# Sheet1.net
KiCad netlist of a schematic drawn in Altium Designer
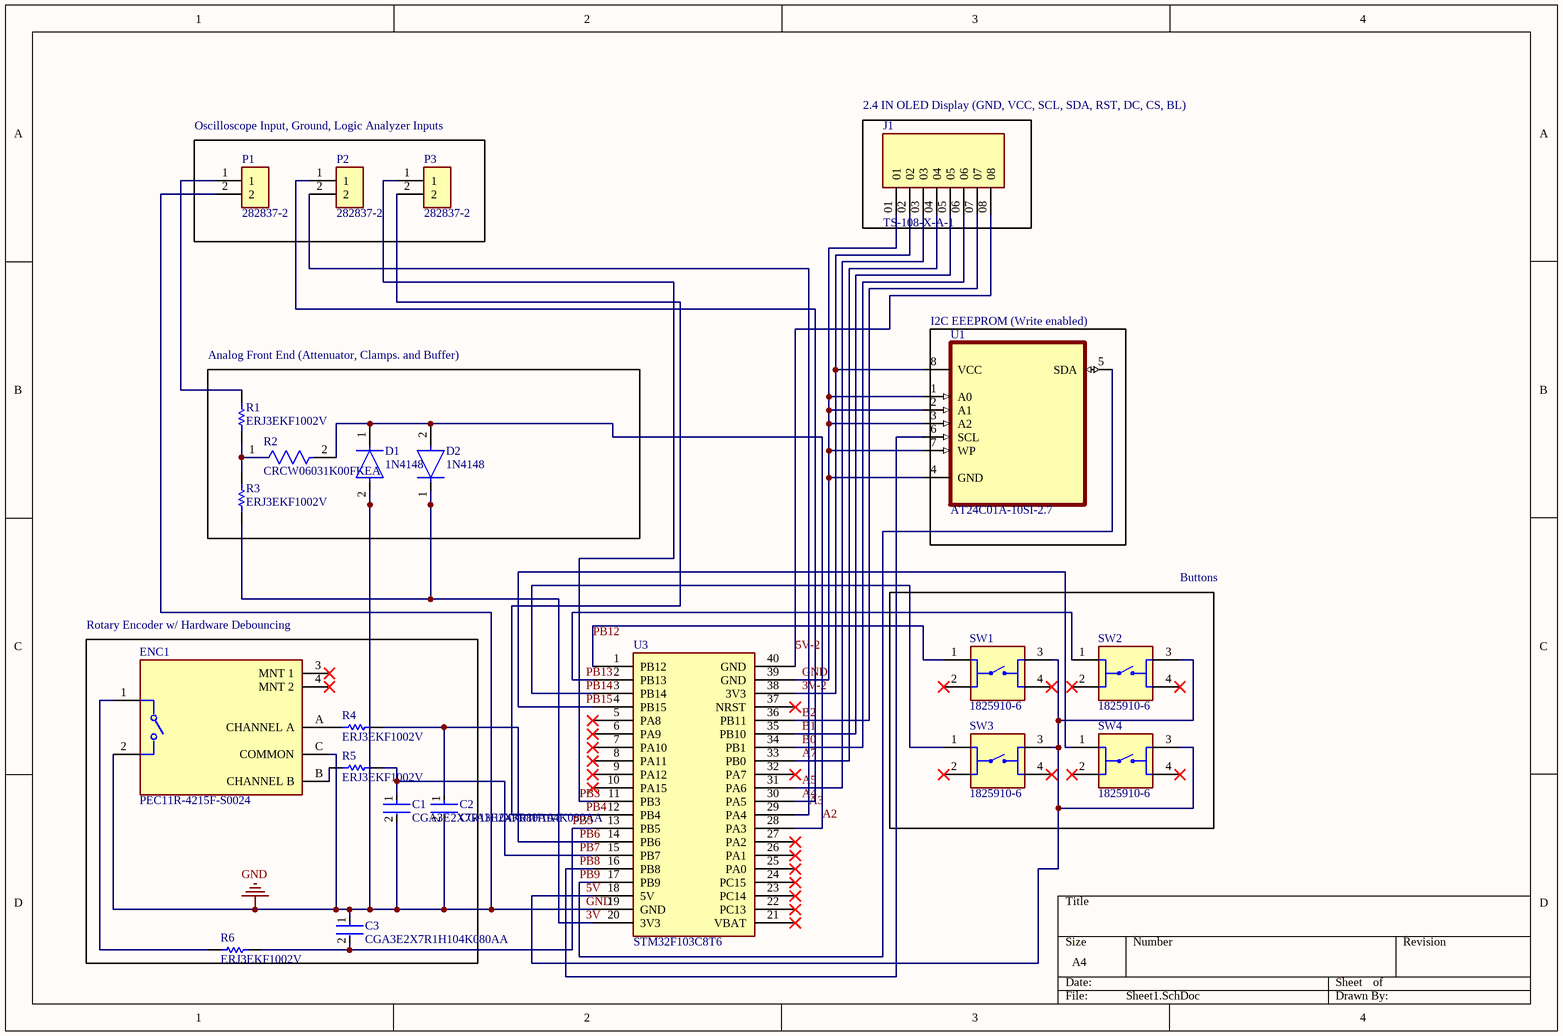
[diagram p0: Sheet1.SchDoc]

(export (version "E")
  (design (tool "Eeschema 10.0.6"))
  (components
    (comp (ref "C1")
      (value "CGA3E2X7R1H104K080AA")
      (footprint "FP-CGA3E-0_3-0_1-IPC_A")
      (description "Cap Ceramic 100nF 50V X7R 10% Pad SMD 0603 +125°C Automotive T/R")
      (fields (field (name "TOLERANCE") "10%") (field (name "VOLTAGE") "50V"))
      (libsource (lib "Altium Content Vault") (part "b4654b650e69147ec39a6b967a45e02"))
    )
    (comp (ref "C2")
      (value "CGA3E2X7R1H104K080AA")
      (footprint "FP-CGA3E-0_3-0_1-IPC_A")
      (description "Cap Ceramic 100nF 50V X7R 10% Pad SMD 0603 +125°C Automotive T/R")
      (fields (field (name "TOLERANCE") "10%") (field (name "VOLTAGE") "50V"))
      (libsource (lib "Altium Content Vault") (part "b4654b650e69147ec39a6b967a45e02"))
    )
    (comp (ref "C3")
      (value "CGA3E2X7R1H104K080AA")
      (footprint "FP-CGA3E-0_3-0_1-IPC_A")
      (description "Cap Ceramic 100nF 50V X7R 10% Pad SMD 0603 +125°C Automotive T/R")
      (fields (field (name "TOLERANCE") "10%") (field (name "VOLTAGE") "50V"))
      (libsource (lib "Altium Content Vault") (part "b4654b650e69147ec39a6b967a45e02"))
    )
    (comp (ref "D1")
      (value "1N4148")
      (footprint "FP-017AG-MFG")
      (description "DIODE GEN PURP 100V 200MA DO35")
      (fields (field (name "VOLTAGE") "100V"))
      (libsource (lib "Altium Content Vault") (part "d7152d700b627762746794eb795d46e"))
    )
    (comp (ref "D2")
      (value "1N4148")
      (footprint "FP-017AG-MFG")
      (description "DIODE GEN PURP 100V 200MA DO35")
      (fields (field (name "VOLTAGE") "100V"))
      (libsource (lib "Altium Content Vault") (part "d7152d700b627762746794eb795d46e"))
    )
    (comp (ref "ENC1")
      (value "PEC11R-4215F-S0024")
      (footprint "FP-PEC11R-4215F-S0024-MFG")
      (description "ROTARY ENCODER MECHANICAL 24PPR")
      (libsource (lib "Altium Content Vault") (part "5f1dd25a4c49fa66e7eeb899730fe11"))
    )
    (comp (ref "J1")
      (value "TS-108-X-A-1")
      (footprint "SAMTEC_TS-108-X-A-1")
      (description "TS Series .100 Single Row Screw Machine Terminal Strip")
      (fields (field (name "MP") "TS-108-G-A-1") (field (name "MF") "Samtec"))
      (libsource (lib "TS-108-X-A-1") (part "TS-108-X-A-1"))
    )
    (comp (ref "P1")
      (value "282837-2")
      (footprint "TE_282837-2")
      (fields (field (name "MF") "TE Connectivity"))
      (libsource (lib "282837-2") (part "282837-2"))
    )
    (comp (ref "P2")
      (value "282837-2")
      (footprint "TE_282837-2")
      (fields (field (name "MF") "TE Connectivity"))
      (libsource (lib "282837-2") (part "282837-2"))
    )
    (comp (ref "P3")
      (value "282837-2")
      (footprint "TE_282837-2")
      (fields (field (name "MF") "TE Connectivity"))
      (libsource (lib "282837-2") (part "282837-2"))
    )
    (comp (ref "R1")
      (value "ERJ3EKF1002V")
      (footprint "RESC1609X55X30LL15T15")
      (description "Chip Resistor, 10 KOhm, +/- 1%, 0.1 W, -55 to 155 degC, 0603 (1608 Metric), RoHS, Tape and Reel")
      (fields (field (name "TOLERANCE") "1%") (field (name "MANUFACTURER") "Panasonic"))
      (libsource (lib "Altium Content Vault") (part "RES-2"))
    )
    (comp (ref "R2")
      (value "CRCW06031K00FKEA")
      (footprint "FP-CRCW0603-e3-MFG")
      (description "RES Thick Film, 1kΩ, 1%, 0.1W, 100ppm/°C, 0603")
      (fields (field (name "TOLERANCE") "1%"))
      (libsource (lib "Altium Content Vault") (part "1029c3af85768c4190bb7ad29bc67b5"))
    )
    (comp (ref "R3")
      (value "ERJ3EKF1002V")
      (footprint "RESC1609X55X30LL15T15")
      (description "Chip Resistor, 10 KOhm, +/- 1%, 0.1 W, -55 to 155 degC, 0603 (1608 Metric), RoHS, Tape and Reel")
      (fields (field (name "TOLERANCE") "1%") (field (name "MANUFACTURER") "Panasonic"))
      (libsource (lib "Altium Content Vault") (part "RES-2"))
    )
    (comp (ref "R4")
      (value "ERJ3EKF1002V")
      (footprint "RESC1609X55X30LL15T15")
      (description "Chip Resistor, 10 KOhm, +/- 1%, 0.1 W, -55 to 155 degC, 0603 (1608 Metric), RoHS, Tape and Reel")
      (fields (field (name "TOLERANCE") "1%") (field (name "MANUFACTURER") "Panasonic"))
      (libsource (lib "Altium Content Vault") (part "RES-2"))
    )
    (comp (ref "R5")
      (value "ERJ3EKF1002V")
      (footprint "RESC1609X55X30LL15T15")
      (description "Chip Resistor, 10 KOhm, +/- 1%, 0.1 W, -55 to 155 degC, 0603 (1608 Metric), RoHS, Tape and Reel")
      (fields (field (name "TOLERANCE") "1%") (field (name "MANUFACTURER") "Panasonic"))
      (libsource (lib "Altium Content Vault") (part "RES-2"))
    )
    (comp (ref "R6")
      (value "ERJ3EKF1002V")
      (footprint "RESC1609X55X30LL15T15")
      (description "Chip Resistor, 10 KOhm, +/- 1%, 0.1 W, -55 to 155 degC, 0603 (1608 Metric), RoHS, Tape and Reel")
      (fields (field (name "TOLERANCE") "1%") (field (name "MANUFACTURER") "Panasonic"))
      (libsource (lib "Altium Content Vault") (part "RES-2"))
    )
    (comp (ref "SW1")
      (value "1825910-6")
      (footprint "SW_1825910-6-4")
      (description "Switch Push Button OFF (ON) SPST Round Button 0.05A 24VDC Momentary Contact PC Pins Thru-Hole")
      (fields (field (name "MF") "TE Connectivity") (field (name "DIGI-KEY_PART_NUMBER") "450-1650-ND"))
      (libsource (lib "1825910-6") (part "1825910-6"))
    )
    (comp (ref "SW2")
      (value "1825910-6")
      (footprint "SW_1825910-6-4")
      (description "Switch Push Button OFF (ON) SPST Round Button 0.05A 24VDC Momentary Contact PC Pins Thru-Hole")
      (fields (field (name "MF") "TE Connectivity") (field (name "DIGI-KEY_PART_NUMBER") "450-1650-ND"))
      (libsource (lib "1825910-6") (part "1825910-6"))
    )
    (comp (ref "SW3")
      (value "1825910-6")
      (footprint "SW_1825910-6-4")
      (description "Switch Push Button OFF (ON) SPST Round Button 0.05A 24VDC Momentary Contact PC Pins Thru-Hole")
      (fields (field (name "MF") "TE Connectivity") (field (name "DIGI-KEY_PART_NUMBER") "450-1650-ND"))
      (libsource (lib "1825910-6") (part "1825910-6"))
    )
    (comp (ref "SW4")
      (value "1825910-6")
      (footprint "SW_1825910-6-4")
      (description "Switch Push Button OFF (ON) SPST Round Button 0.05A 24VDC Momentary Contact PC Pins Thru-Hole")
      (fields (field (name "MF") "TE Connectivity") (field (name "DIGI-KEY_PART_NUMBER") "450-1650-ND"))
      (libsource (lib "1825910-6") (part "1825910-6"))
    )
    (comp (ref "U1")
      (value "AT24C01A-10SI-2.7")
      (footprint "SOIC127P600X175-8N")
      (description "Two-wire Serial EEPROM")
      (libsource (lib "AT24C01A-10SI-2.7") (part "AT24C01A-10SI-2.7"))
    )
    (comp (ref "U3")
      (value "STM32F103C8T6")
      (footprint "ZC323000:MODULE_ZC323000")
      (description "Designed By @Alixahedi")
      (libsource (lib "Stm32 Blue Pill") (part "BluePill"))
    )
  )
  (nets
    (net (code "1") (name "/3V") (class "Default")
      (node (ref "D2") (pin "1") (pinfunction "C_1") (pintype "passive"))
      (node (ref "R3") (pin "2") (pinfunction "2_2") (pintype "passive"))
      (node (ref "U3") (pin "20") (pinfunction "3V3_20") (pintype "passive"))
    )
    (net (code "2") (name "/3V-2") (class "Default")
      (node (ref "J1") (pin "02") (pinfunction "02_02") (pintype "passive"))
      (node (ref "U1") (pin "8") (pinfunction "VCC_8") (pintype "power_in"))
      (node (ref "U3") (pin "38") (pinfunction "3V3_38") (pintype "passive"))
    )
    (net (code "3") (name "/5V") (class "Default")
      (node (ref "SW1") (pin "3") (pinfunction "3_3") (pintype "passive"))
      (node (ref "SW2") (pin "3") (pinfunction "3_3") (pintype "passive"))
      (node (ref "SW3") (pin "3") (pinfunction "3_3") (pintype "passive"))
      (node (ref "SW4") (pin "3") (pinfunction "3_3") (pintype "passive"))
      (node (ref "U3") (pin "18") (pinfunction "5V_18") (pintype "passive"))
    )
    (net (code "4") (name "/5V-2") (class "Default")
      (node (ref "J1") (pin "08") (pinfunction "08_08") (pintype "passive"))
      (node (ref "U3") (pin "40") (pinfunction "GND_40") (pintype "passive"))
    )
    (net (code "5") (name "/A2") (class "Default")
      (node (ref "D1") (pin "1") (pinfunction "C_1") (pintype "passive"))
      (node (ref "D2") (pin "2") (pinfunction "A_2") (pintype "passive"))
      (node (ref "R2") (pin "2") (pinfunction "2_2") (pintype "passive"))
      (node (ref "U3") (pin "28") (pinfunction "PA3_28") (pintype "passive"))
    )
    (net (code "6") (name "/A3") (class "Default")
      (node (ref "P2") (pin "2") (pinfunction "2_2") (pintype "passive"))
      (node (ref "U3") (pin "29") (pinfunction "PA4_29") (pintype "passive"))
    )
    (net (code "7") (name "/A4") (class "Default")
      (node (ref "P2") (pin "1") (pinfunction "1_1") (pintype "passive"))
      (node (ref "U3") (pin "30") (pinfunction "PA5_30") (pintype "passive"))
    )
    (net (code "8") (name "/A5") (class "Default")
      (node (ref "J1") (pin "03") (pinfunction "03_03") (pintype "passive"))
      (node (ref "U3") (pin "31") (pinfunction "PA6_31") (pintype "passive"))
    )
    (net (code "9") (name "/A7") (class "Default")
      (node (ref "J1") (pin "04") (pinfunction "04_04") (pintype "passive"))
      (node (ref "U3") (pin "33") (pinfunction "PB0_33") (pintype "passive"))
    )
    (net (code "10") (name "/B0") (class "Default")
      (node (ref "J1") (pin "06") (pinfunction "06_06") (pintype "passive"))
      (node (ref "U3") (pin "34") (pinfunction "PB1_34") (pintype "passive"))
    )
    (net (code "11") (name "/B1") (class "Default")
      (node (ref "J1") (pin "05") (pinfunction "05_05") (pintype "passive"))
      (node (ref "U3") (pin "35") (pinfunction "PB10_35") (pintype "passive"))
    )
    (net (code "12") (name "/B2") (class "Default")
      (node (ref "J1") (pin "07") (pinfunction "07_07") (pintype "passive"))
      (node (ref "U3") (pin "36") (pinfunction "PB11_36") (pintype "passive"))
    )
    (net (code "13") (name "/PB3") (class "Default")
      (node (ref "P3") (pin "1") (pinfunction "1_1") (pintype "passive"))
      (node (ref "U3") (pin "11") (pinfunction "PB3_11") (pintype "passive"))
    )
    (net (code "14") (name "/PB4") (class "Default")
      (node (ref "P3") (pin "2") (pinfunction "2_2") (pintype "passive"))
      (node (ref "U3") (pin "12") (pinfunction "PB4_12") (pintype "passive"))
    )
    (net (code "15") (name "/PB5") (class "Default")
      (node (ref "C3") (pin "2") (pinfunction "2_2") (pintype "passive"))
      (node (ref "R6") (pin "2") (pinfunction "2_2") (pintype "passive"))
      (node (ref "U3") (pin "13") (pinfunction "PB5_13") (pintype "passive"))
    )
    (net (code "16") (name "/PB6") (class "Default")
      (node (ref "C2") (pin "1") (pinfunction "1_1") (pintype "passive"))
      (node (ref "R4") (pin "2") (pinfunction "2_2") (pintype "passive"))
      (node (ref "U3") (pin "14") (pinfunction "PB6_14") (pintype "passive"))
    )
    (net (code "17") (name "/PB7") (class "Default")
      (node (ref "C1") (pin "1") (pinfunction "1_1") (pintype "passive"))
      (node (ref "R5") (pin "2") (pinfunction "2_2") (pintype "passive"))
      (node (ref "U3") (pin "15") (pinfunction "PB7_15") (pintype "passive"))
    )
    (net (code "18") (name "/PB8") (class "Default")
      (node (ref "U1") (pin "6") (pinfunction "SCL_6") (pintype "input"))
      (node (ref "U3") (pin "16") (pinfunction "PB8_16") (pintype "passive"))
    )
    (net (code "19") (name "/PB9") (class "Default")
      (node (ref "U1") (pin "5") (pinfunction "SDA_5") (pintype "bidirectional"))
      (node (ref "U3") (pin "17") (pinfunction "PB9_17") (pintype "passive"))
    )
    (net (code "20") (name "/PB12") (class "Default")
      (node (ref "SW1") (pin "1") (pinfunction "1_1") (pintype "passive"))
      (node (ref "U3") (pin "1") (pinfunction "PB12_1") (pintype "passive"))
    )
    (net (code "21") (name "/PB13") (class "Default")
      (node (ref "SW2") (pin "1") (pinfunction "1_1") (pintype "passive"))
      (node (ref "U3") (pin "2") (pinfunction "PB13_2") (pintype "passive"))
    )
    (net (code "22") (name "/PB14") (class "Default")
      (node (ref "SW3") (pin "1") (pinfunction "1_1") (pintype "passive"))
      (node (ref "U3") (pin "3") (pinfunction "PB14_3") (pintype "passive"))
    )
    (net (code "23") (name "/PB15") (class "Default")
      (node (ref "SW4") (pin "1") (pinfunction "1_1") (pintype "passive"))
      (node (ref "U3") (pin "4") (pinfunction "PB15_4") (pintype "passive"))
    )
    (net (code "24") (name "GND") (class "Default")
      (node (ref "C1") (pin "2") (pinfunction "2_2") (pintype "passive"))
      (node (ref "C2") (pin "2") (pinfunction "2_2") (pintype "passive"))
      (node (ref "C3") (pin "1") (pinfunction "1_1") (pintype "passive"))
      (node (ref "D1") (pin "2") (pinfunction "A_2") (pintype "passive"))
      (node (ref "ENC1") (pin "2") (pinfunction "2_2") (pintype "passive"))
      (node (ref "ENC1") (pin "C") (pinfunction "COMMON_C") (pintype "passive"))
      (node (ref "J1") (pin "01") (pinfunction "01_01") (pintype "passive"))
      (node (ref "P1") (pin "2") (pinfunction "2_2") (pintype "passive"))
      (node (ref "U1") (pin "1") (pinfunction "A0_1") (pintype "input"))
      (node (ref "U1") (pin "2") (pinfunction "A1_2") (pintype "input"))
      (node (ref "U1") (pin "3") (pinfunction "A2_3") (pintype "input"))
      (node (ref "U1") (pin "4") (pinfunction "GND_4") (pintype "passive"))
      (node (ref "U1") (pin "7") (pinfunction "WP_7") (pintype "input"))
      (node (ref "U3") (pin "19") (pinfunction "GND_19") (pintype "passive"))
      (node (ref "U3") (pin "39") (pinfunction "GND_39") (pintype "passive"))
    )
    (net (code "25") (name "Net-(ENC1-CHANNEL_A)") (class "Default")
      (node (ref "ENC1") (pin "A") (pinfunction "CHANNEL_A_A") (pintype "passive"))
      (node (ref "R4") (pin "1") (pinfunction "1_1") (pintype "passive"))
    )
    (net (code "26") (name "Net-(ENC1-CHANNEL_B)") (class "Default")
      (node (ref "ENC1") (pin "B") (pinfunction "CHANNEL_B_B") (pintype "passive"))
      (node (ref "R5") (pin "1") (pinfunction "1_1") (pintype "passive"))
    )
    (net (code "27") (name "Net-(ENC1-Pad1)") (class "Default")
      (node (ref "ENC1") (pin "1") (pinfunction "1_1") (pintype "passive"))
      (node (ref "R6") (pin "1") (pinfunction "1_1") (pintype "passive"))
    )
    (net (code "28") (name "Net-(P1-Pad1)") (class "Default")
      (node (ref "P1") (pin "1") (pinfunction "1_1") (pintype "passive"))
      (node (ref "R1") (pin "1") (pinfunction "1_1") (pintype "passive"))
    )
    (net (code "29") (name "Net-(R1-Pad2)") (class "Default")
      (node (ref "R1") (pin "2") (pinfunction "2_2") (pintype "passive"))
      (node (ref "R2") (pin "1") (pinfunction "1_1") (pintype "passive"))
      (node (ref "R3") (pin "1") (pinfunction "1_1") (pintype "passive"))
    )
    (net (code "30") (name "unconnected-(ENC1-MNT_1-Pad3)") (class "Default")
      (node (ref "ENC1") (pin "3") (pinfunction "MNT_1_3") (pintype "passive+no_connect"))
    )
    (net (code "31") (name "unconnected-(ENC1-MNT_2-Pad4)") (class "Default")
      (node (ref "ENC1") (pin "4") (pinfunction "MNT_2_4") (pintype "passive+no_connect"))
    )
    (net (code "32") (name "unconnected-(SW1-Pad2)") (class "Default")
      (node (ref "SW1") (pin "2") (pinfunction "2_2") (pintype "passive+no_connect"))
    )
    (net (code "33") (name "unconnected-(SW1-Pad4)") (class "Default")
      (node (ref "SW1") (pin "4") (pinfunction "4_4") (pintype "passive+no_connect"))
    )
    (net (code "34") (name "unconnected-(SW2-Pad2)") (class "Default")
      (node (ref "SW2") (pin "2") (pinfunction "2_2") (pintype "passive+no_connect"))
    )
    (net (code "35") (name "unconnected-(SW2-Pad4)") (class "Default")
      (node (ref "SW2") (pin "4") (pinfunction "4_4") (pintype "passive+no_connect"))
    )
    (net (code "36") (name "unconnected-(SW3-Pad2)") (class "Default")
      (node (ref "SW3") (pin "2") (pinfunction "2_2") (pintype "passive+no_connect"))
    )
    (net (code "37") (name "unconnected-(SW3-Pad4)") (class "Default")
      (node (ref "SW3") (pin "4") (pinfunction "4_4") (pintype "passive+no_connect"))
    )
    (net (code "38") (name "unconnected-(SW4-Pad2)") (class "Default")
      (node (ref "SW4") (pin "2") (pinfunction "2_2") (pintype "passive+no_connect"))
    )
    (net (code "39") (name "unconnected-(SW4-Pad4)") (class "Default")
      (node (ref "SW4") (pin "4") (pinfunction "4_4") (pintype "passive+no_connect"))
    )
    (net (code "40") (name "unconnected-(U3-NRST-Pad37)") (class "Default")
      (node (ref "U3") (pin "37") (pinfunction "NRST_37") (pintype "passive+no_connect"))
    )
    (net (code "41") (name "unconnected-(U3-PA0-Pad25)") (class "Default")
      (node (ref "U3") (pin "25") (pinfunction "PA0_25") (pintype "passive+no_connect"))
    )
    (net (code "42") (name "unconnected-(U3-PA1-Pad26)") (class "Default")
      (node (ref "U3") (pin "26") (pinfunction "PA1_26") (pintype "passive+no_connect"))
    )
    (net (code "43") (name "unconnected-(U3-PA2-Pad27)") (class "Default")
      (node (ref "U3") (pin "27") (pinfunction "PA2_27") (pintype "passive+no_connect"))
    )
    (net (code "44") (name "unconnected-(U3-PA7-Pad32)") (class "Default")
      (node (ref "U3") (pin "32") (pinfunction "PA7_32") (pintype "passive+no_connect"))
    )
    (net (code "45") (name "unconnected-(U3-PA8-Pad5)") (class "Default")
      (node (ref "U3") (pin "5") (pinfunction "PA8_5") (pintype "passive+no_connect"))
    )
    (net (code "46") (name "unconnected-(U3-PA9-Pad6)") (class "Default")
      (node (ref "U3") (pin "6") (pinfunction "PA9_6") (pintype "passive+no_connect"))
    )
    (net (code "47") (name "unconnected-(U3-PA10-Pad7)") (class "Default")
      (node (ref "U3") (pin "7") (pinfunction "PA10_7") (pintype "passive+no_connect"))
    )
    (net (code "48") (name "unconnected-(U3-PA11-Pad8)") (class "Default")
      (node (ref "U3") (pin "8") (pinfunction "PA11_8") (pintype "passive+no_connect"))
    )
    (net (code "49") (name "unconnected-(U3-PA12-Pad9)") (class "Default")
      (node (ref "U3") (pin "9") (pinfunction "PA12_9") (pintype "passive+no_connect"))
    )
    (net (code "50") (name "unconnected-(U3-PA15-Pad10)") (class "Default")
      (node (ref "U3") (pin "10") (pinfunction "PA15_10") (pintype "passive+no_connect"))
    )
    (net (code "51") (name "unconnected-(U3-PC13-Pad22)") (class "Default")
      (node (ref "U3") (pin "22") (pinfunction "PC13_22") (pintype "passive+no_connect"))
    )
    (net (code "52") (name "unconnected-(U3-PC14-Pad23)") (class "Default")
      (node (ref "U3") (pin "23") (pinfunction "PC14_23") (pintype "passive+no_connect"))
    )
    (net (code "53") (name "unconnected-(U3-PC15-Pad24)") (class "Default")
      (node (ref "U3") (pin "24") (pinfunction "PC15_24") (pintype "passive+no_connect"))
    )
    (net (code "54") (name "unconnected-(U3-VBAT-Pad21)") (class "Default")
      (node (ref "U3") (pin "21") (pinfunction "VBAT_21") (pintype "passive+no_connect"))
    )
  )
)
